# GF_RemoteDoorOpener_TX.net
KiCad netlist of a schematic drawn in EAGLE
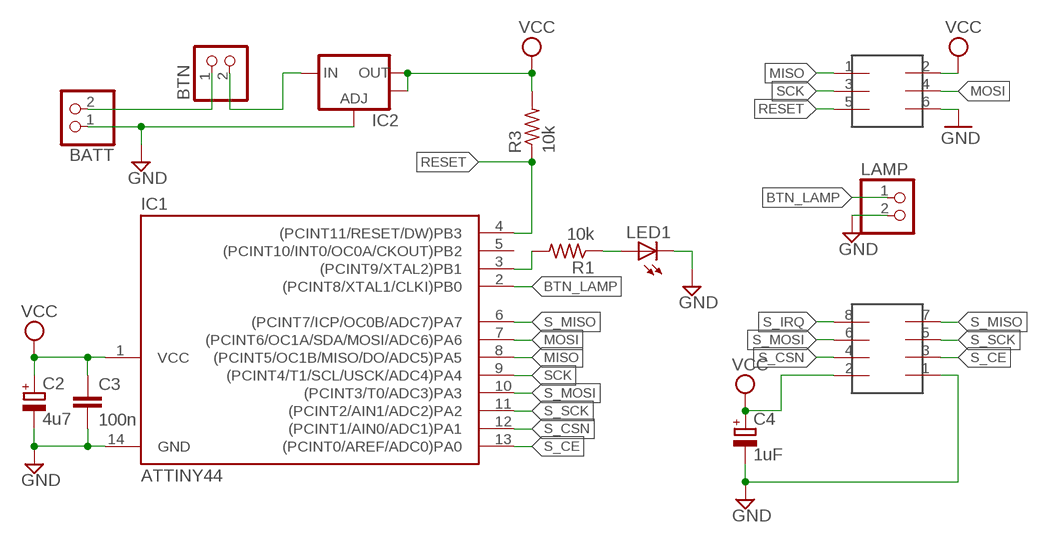
[diagram p0: schematic, sheet 1]

(export (version "E")
  (design (tool "Eeschema 10.0.6"))
  (components
    (comp (ref "BATT")
      (value "PINHD-1X2")
      (footprint "eagle-import:1X02")
      (libsource (lib "eagle-import") (part "PINHD-1X2"))
    )
    (comp (ref "BTN")
      (value "PINHD-1X2")
      (footprint "eagle-import:1X02")
      (libsource (lib "eagle-import") (part "PINHD-1X2"))
    )
    (comp (ref "C2")
      (value "4u7")
      (footprint "eagle-import:SMC_A")
      (libsource (lib "eagle-import") (part "CPOL-EUSMCA"))
    )
    (comp (ref "C3")
      (value "100n")
      (footprint "eagle-import:C0603")
      (libsource (lib "eagle-import") (part "C-EUC0603"))
    )
    (comp (ref "C4")
      (value "1uF")
      (footprint "eagle-import:SMC_A")
      (libsource (lib "eagle-import") (part "CPOL-EUSMCA"))
    )
    (comp (ref "IC1")
      (value "ATTINY44")
      (footprint "eagle-import:SOIC14")
      (libsource (lib "eagle-import") (part "ATTINY24/44/84-SSU"))
    )
    (comp (ref "IC2")
      (value "V_REG_LM1117SOT223")
      (footprint "eagle-import:SOT223")
      (libsource (lib "eagle-import") (part "V_REG_LM1117SOT223"))
    )
    (comp (ref "ISP")
      (value "2X3HEADER")
      (footprint "eagle-import:2X3_SMD")
      (libsource (lib "eagle-import") (part "2X3HEADER"))
    )
    (comp (ref "LAMP")
      (value "PINHD-1X2")
      (footprint "eagle-import:1X02")
      (libsource (lib "eagle-import") (part "PINHD-1X2"))
    )
    (comp (ref "LED1")
      (value "LEDCHIPLED_1206")
      (footprint "eagle-import:CHIPLED_1206")
      (libsource (lib "eagle-import") (part "LEDCHIPLED_1206"))
    )
    (comp (ref "R1")
      (value "10k")
      (footprint "eagle-import:R0603")
      (libsource (lib "eagle-import") (part "R-US_R0603"))
    )
    (comp (ref "R3")
      (value "10k")
      (footprint "eagle-import:R0603")
      (libsource (lib "eagle-import") (part "R-US_R0603"))
    )
    (comp (ref "U$2")
      (value "2X4HEADER")
      (footprint "eagle-import:2X4_SMD")
      (libsource (lib "eagle-import") (part "2X4HEADER"))
    )
  )
  (nets
    (net (code "1") (name "BTN_LAMP") (class "Default")
      (node (ref "IC1") (pin "2") (pinfunction "(PCINT8/XTAL1/CLKI)PB0_2") (pintype "bidirectional"))
      (node (ref "LAMP") (pin "1") (pinfunction "1_1") (pintype "passive"))
    )
    (net (code "2") (name "GND") (class "Default")
      (node (ref "BATT") (pin "1") (pinfunction "1_1") (pintype "passive"))
      (node (ref "C2") (pin "-") (pinfunction "-_-") (pintype "passive"))
      (node (ref "C3") (pin "2") (pinfunction "2_2") (pintype "passive"))
      (node (ref "C4") (pin "-") (pinfunction "-_-") (pintype "passive"))
      (node (ref "IC1") (pin "14") (pinfunction "GND_14") (pintype "power_in"))
      (node (ref "IC2") (pin "1") (pinfunction "ADJ_1") (pintype "input"))
      (node (ref "ISP") (pin "6") (pinfunction "P$6_6") (pintype "bidirectional"))
      (node (ref "LAMP") (pin "2") (pinfunction "2_2") (pintype "passive"))
      (node (ref "LED1") (pin "C") (pinfunction "C_C") (pintype "passive"))
      (node (ref "U$2") (pin "1") (pinfunction "P$1_1") (pintype "bidirectional"))
    )
    (net (code "3") (name "MISO") (class "Default")
      (node (ref "IC1") (pin "8") (pinfunction "(PCINT5/OC1B/MISO/DO/ADC5)PA5_8") (pintype "bidirectional"))
      (node (ref "ISP") (pin "1") (pinfunction "P$1_1") (pintype "bidirectional"))
    )
    (net (code "4") (name "MOSI") (class "Default")
      (node (ref "IC1") (pin "7") (pinfunction "(PCINT6/OC1A/SDA/MOSI/ADC6)PA6_7") (pintype "bidirectional"))
      (node (ref "ISP") (pin "4") (pinfunction "P$4_4") (pintype "bidirectional"))
    )
    (net (code "5") (name "Net-(BATT-Pad2)") (class "Default")
      (node (ref "BATT") (pin "2") (pinfunction "2_2") (pintype "passive"))
      (node (ref "BTN") (pin "1") (pinfunction "1_1") (pintype "passive"))
    )
    (net (code "6") (name "Net-(IC1-(PCINT9{slash}XTAL2)PB1)") (class "Default")
      (node (ref "IC1") (pin "3") (pinfunction "(PCINT9/XTAL2)PB1_3") (pintype "bidirectional"))
      (node (ref "R1") (pin "2") (pinfunction "2_2") (pintype "passive"))
    )
    (net (code "7") (name "Net-(IC2-IN)") (class "Default")
      (node (ref "BTN") (pin "2") (pinfunction "2_2") (pintype "passive"))
      (node (ref "IC2") (pin "3") (pinfunction "IN_3") (pintype "input"))
    )
    (net (code "8") (name "Net-(LED1-PadA)") (class "Default")
      (node (ref "LED1") (pin "A") (pinfunction "A_A") (pintype "passive"))
      (node (ref "R1") (pin "1") (pinfunction "1_1") (pintype "passive"))
    )
    (net (code "9") (name "RESET") (class "Default")
      (node (ref "IC1") (pin "4") (pinfunction "(PCINT11/RESET/DW)PB3_4") (pintype "bidirectional"))
      (node (ref "ISP") (pin "5") (pinfunction "P$5_5") (pintype "bidirectional"))
      (node (ref "R3") (pin "1") (pinfunction "1_1") (pintype "passive"))
    )
    (net (code "10") (name "SCK") (class "Default")
      (node (ref "IC1") (pin "9") (pinfunction "(PCINT4/T1/SCL/USCK/ADC4)PA4_9") (pintype "bidirectional"))
      (node (ref "ISP") (pin "3") (pinfunction "P$3_3") (pintype "bidirectional"))
    )
    (net (code "11") (name "S_CE") (class "Default")
      (node (ref "IC1") (pin "13") (pinfunction "(PCINT0/AREF/ADC0)PA0_13") (pintype "bidirectional"))
      (node (ref "U$2") (pin "3") (pinfunction "P$3_3") (pintype "bidirectional"))
    )
    (net (code "12") (name "S_CSN") (class "Default")
      (node (ref "IC1") (pin "12") (pinfunction "(PCINT1/AIN0/ADC1)PA1_12") (pintype "bidirectional"))
      (node (ref "U$2") (pin "4") (pinfunction "P$4_4") (pintype "bidirectional"))
    )
    (net (code "13") (name "S_IRQ") (class "Default")
      (node (ref "U$2") (pin "8") (pinfunction "P$8_8") (pintype "bidirectional"))
    )
    (net (code "14") (name "S_MISO") (class "Default")
      (node (ref "IC1") (pin "6") (pinfunction "(PCINT7/ICP/OC0B/ADC7)PA7_6") (pintype "bidirectional"))
      (node (ref "U$2") (pin "7") (pinfunction "P$7_7") (pintype "bidirectional"))
    )
    (net (code "15") (name "S_MOSI") (class "Default")
      (node (ref "IC1") (pin "10") (pinfunction "(PCINT3/T0/ADC3)PA3_10") (pintype "bidirectional"))
      (node (ref "U$2") (pin "6") (pinfunction "P$6_6") (pintype "bidirectional"))
    )
    (net (code "16") (name "S_SCK") (class "Default")
      (node (ref "IC1") (pin "11") (pinfunction "(PCINT2/AIN1/ADC2)PA2_11") (pintype "bidirectional"))
      (node (ref "U$2") (pin "5") (pinfunction "P$5_5") (pintype "bidirectional"))
    )
    (net (code "17") (name "VCC") (class "Default")
      (node (ref "C2") (pin "+") (pinfunction "+_+") (pintype "passive"))
      (node (ref "C3") (pin "1") (pinfunction "1_1") (pintype "passive"))
      (node (ref "C4") (pin "+") (pinfunction "+_+") (pintype "passive"))
      (node (ref "IC1") (pin "1") (pinfunction "VCC_1") (pintype "power_in"))
      (node (ref "IC2") (pin "2") (pinfunction "OUT_2") (pintype "output"))
      (node (ref "IC2") (pin "4") (pinfunction "OUT_4") (pintype "output"))
      (node (ref "ISP") (pin "2") (pinfunction "P$2_2") (pintype "bidirectional"))
      (node (ref "R3") (pin "2") (pinfunction "2_2") (pintype "passive"))
      (node (ref "U$2") (pin "2") (pinfunction "P$2_2") (pintype "bidirectional"))
    )
    (net (code "18") (name "unconnected-(IC1-(PCINT10{slash}INT0{slash}OC0A{slash}CKOUT)PB2-Pad5)") (class "Default")
      (node (ref "IC1") (pin "5") (pinfunction "(PCINT10/INT0/OC0A/CKOUT)PB2_5") (pintype "bidirectional"))
    )
  )
)
